# SCH_UD-05-PCB-design-David-Sanchez_2025-.net
KiCad netlist of a schematic drawn in EasyEDA
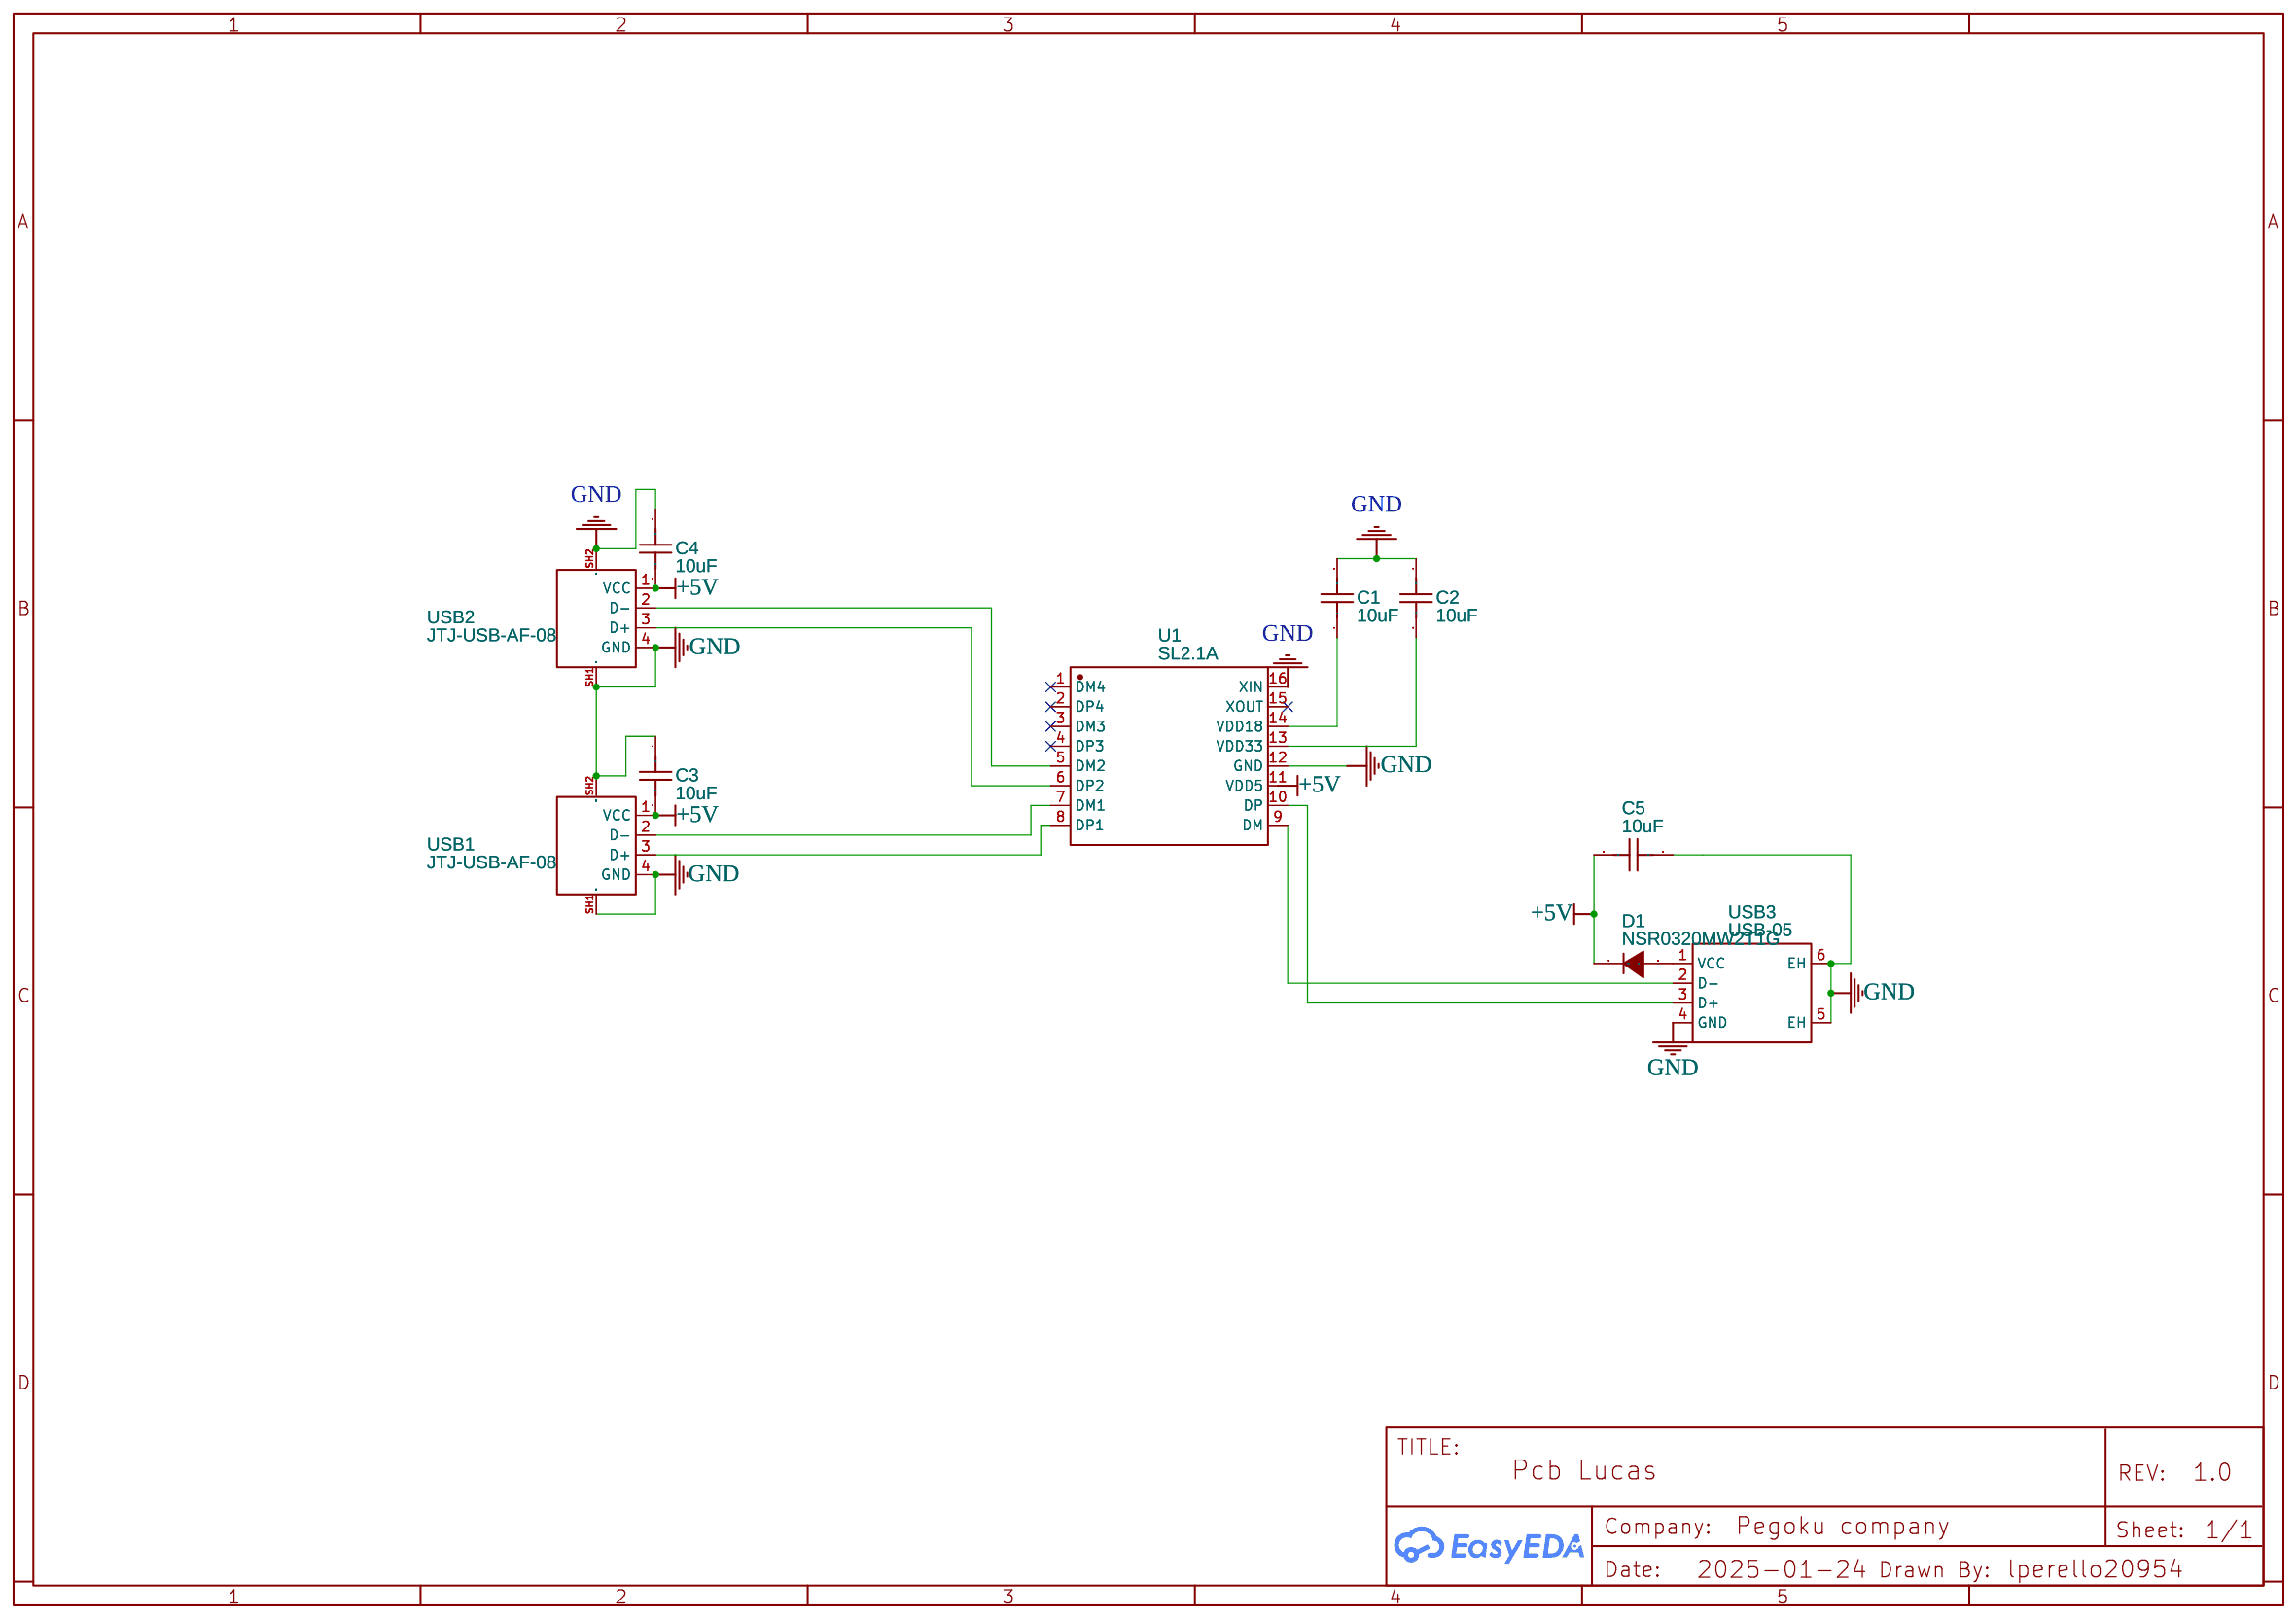
[diagram p0: schematic sheet]

(export (version "E")
  (design (tool "Eeschema 10.0.6"))
  (components
    (comp (ref "C1")
      (value "10uF")
      (fields
        (field (name "Manufacturer Part") "CL10A106KP8NNNC")
        (field (name "Manufacturer") "SAMSUNG(三星)")
      )
      (libsource (lib "") (part "CL10A106KP8NNNC_1"))
    )
    (comp (ref "C2")
      (value "10uF")
      (fields
        (field (name "Manufacturer Part") "CL10A106KP8NNNC")
        (field (name "Manufacturer") "SAMSUNG(三星)")
      )
      (libsource (lib "") (part "CL10A106KP8NNNC"))
    )
    (comp (ref "C3")
      (value "10uF")
      (fields
        (field (name "Manufacturer Part") "CL10A106KP8NNNC")
        (field (name "Manufacturer") "SAMSUNG(三星)")
      )
      (libsource (lib "") (part "CL10A106KP8NNNC"))
    )
    (comp (ref "C4")
      (value "10uF")
      (fields
        (field (name "Manufacturer Part") "CL10A106KP8NNNC")
        (field (name "Manufacturer") "SAMSUNG(三星)")
      )
      (libsource (lib "") (part "CL10A106KP8NNNC"))
    )
    (comp (ref "C5")
      (value "10uF")
      (fields
        (field (name "Manufacturer Part") "CL10A106KP8NNNC")
        (field (name "Manufacturer") "SAMSUNG(三星)")
      )
      (libsource (lib "") (part "CL10A106KP8NNNC_2"))
    )
    (comp (ref "D1")
      (value "NSR0320MW2T1G")
      (fields (field (name "Manufacturer") "onsemi(安森美)"))
      (libsource (lib "") (part "NSR0320MW2T1G"))
    )
    (comp (ref "U1")
      (value "SL2.1A")
      (fields (field (name "Manufacturer") "CoreChips(和芯润德)"))
      (libsource (lib "") (part "SL2.1A"))
    )
    (comp (ref "USB1")
      (value "JTJ-USB-AF-08")
      (fields (field (name "Manufacturer Part") "902-131A1011D10100") (field (name "Manufacturer") "精拓金"))
      (libsource (lib "") (part "JTJ-USB-AF-08"))
    )
    (comp (ref "USB2")
      (value "JTJ-USB-AF-08")
      (fields (field (name "Manufacturer Part") "902-131A1011D10100") (field (name "Manufacturer") "精拓金"))
      (libsource (lib "") (part "JTJ-USB-AF-08"))
    )
    (comp (ref "USB3")
      (value "USB-05")
      (fields (field (name "Manufacturer") "SOFNG(硕方)"))
      (libsource (lib "") (part "USB-05"))
    )
  )
  (nets
    (net (code "1") (name "+5V") (class "Default")
      (node (ref "C3") (pin "2") (pinfunction "2_2") (pintype "unspecified"))
      (node (ref "C4") (pin "2") (pinfunction "2_2") (pintype "unspecified"))
      (node (ref "C5") (pin "2") (pinfunction "2_2") (pintype "unspecified"))
      (node (ref "D1") (pin "1") (pinfunction "C_1") (pintype "unspecified"))
      (node (ref "U1") (pin "11") (pinfunction "VDD5_11") (pintype "unspecified"))
      (node (ref "USB1") (pin "1") (pinfunction "VCC_1") (pintype "input"))
      (node (ref "USB2") (pin "1") (pinfunction "VCC_1") (pintype "input"))
    )
    (net (code "2") (name "GND") (class "Default")
      (node (ref "C1") (pin "2") (pinfunction "2_2") (pintype "unspecified"))
      (node (ref "C2") (pin "1") (pinfunction "1_1") (pintype "unspecified"))
      (node (ref "C3") (pin "1") (pinfunction "1_1") (pintype "unspecified"))
      (node (ref "C4") (pin "1") (pinfunction "1_1") (pintype "unspecified"))
      (node (ref "C5") (pin "1") (pinfunction "1_1") (pintype "unspecified"))
      (node (ref "U1") (pin "12") (pinfunction "GND_12") (pintype "unspecified"))
      (node (ref "U1") (pin "16") (pinfunction "XIN_16") (pintype "unspecified"))
      (node (ref "USB1") (pin "4") (pinfunction "GND_4") (pintype "input"))
      (node (ref "USB1") (pin "SH1") (pinfunction "SH1_SH1") (pintype "unspecified"))
      (node (ref "USB1") (pin "SH2") (pinfunction "SH2_SH2") (pintype "unspecified"))
      (node (ref "USB2") (pin "4") (pinfunction "GND_4") (pintype "input"))
      (node (ref "USB2") (pin "SH1") (pinfunction "SH1_SH1") (pintype "unspecified"))
      (node (ref "USB2") (pin "SH2") (pinfunction "SH2_SH2") (pintype "unspecified"))
      (node (ref "USB3") (pin "4") (pinfunction "GND_4") (pintype "input"))
      (node (ref "USB3") (pin "5") (pinfunction "EH_5") (pintype "unspecified"))
      (node (ref "USB3") (pin "6") (pinfunction "EH_6") (pintype "unspecified"))
    )
    (net (code "3") (name "Net-(D1-A)") (class "Default")
      (node (ref "D1") (pin "2") (pinfunction "A_2") (pintype "unspecified"))
      (node (ref "USB3") (pin "1") (pinfunction "VCC_1") (pintype "input"))
    )
    (net (code "4") (name "Net-(U1-DM)") (class "Default")
      (node (ref "U1") (pin "9") (pinfunction "DM_9") (pintype "unspecified"))
      (node (ref "USB3") (pin "2") (pinfunction "D-_2") (pintype "input"))
    )
    (net (code "5") (name "Net-(U1-DM1)") (class "Default")
      (node (ref "U1") (pin "7") (pinfunction "DM1_7") (pintype "unspecified"))
      (node (ref "USB1") (pin "2") (pinfunction "D-_2") (pintype "input"))
    )
    (net (code "6") (name "Net-(U1-DM2)") (class "Default")
      (node (ref "U1") (pin "5") (pinfunction "DM2_5") (pintype "unspecified"))
      (node (ref "USB2") (pin "2") (pinfunction "D-_2") (pintype "input"))
    )
    (net (code "7") (name "Net-(U1-DP)") (class "Default")
      (node (ref "U1") (pin "10") (pinfunction "DP_10") (pintype "unspecified"))
      (node (ref "USB3") (pin "3") (pinfunction "D+_3") (pintype "input"))
    )
    (net (code "8") (name "Net-(U1-DP1)") (class "Default")
      (node (ref "U1") (pin "8") (pinfunction "DP1_8") (pintype "unspecified"))
      (node (ref "USB1") (pin "3") (pinfunction "D+_3") (pintype "input"))
    )
    (net (code "9") (name "Net-(U1-DP2)") (class "Default")
      (node (ref "U1") (pin "6") (pinfunction "DP2_6") (pintype "unspecified"))
      (node (ref "USB2") (pin "3") (pinfunction "D+_3") (pintype "input"))
    )
    (net (code "10") (name "Net-(U1-VDD18)") (class "Default")
      (node (ref "C1") (pin "1") (pinfunction "1_1") (pintype "unspecified"))
      (node (ref "U1") (pin "14") (pinfunction "VDD18_14") (pintype "unspecified"))
    )
    (net (code "11") (name "Net-(U1-VDD33)") (class "Default")
      (node (ref "C2") (pin "2") (pinfunction "2_2") (pintype "unspecified"))
      (node (ref "U1") (pin "13") (pinfunction "VDD33_13") (pintype "unspecified"))
    )
    (net (code "12") (name "unconnected-(U1-DM3-Pad3)") (class "Default")
      (node (ref "U1") (pin "3") (pinfunction "DM3_3") (pintype "unspecified+no_connect"))
    )
    (net (code "13") (name "unconnected-(U1-DM4-Pad1)") (class "Default")
      (node (ref "U1") (pin "1") (pinfunction "DM4_1") (pintype "unspecified+no_connect"))
    )
    (net (code "14") (name "unconnected-(U1-DP3-Pad4)") (class "Default")
      (node (ref "U1") (pin "4") (pinfunction "DP3_4") (pintype "unspecified+no_connect"))
    )
    (net (code "15") (name "unconnected-(U1-DP4-Pad2)") (class "Default")
      (node (ref "U1") (pin "2") (pinfunction "DP4_2") (pintype "unspecified+no_connect"))
    )
    (net (code "16") (name "unconnected-(U1-XOUT-Pad15)") (class "Default")
      (node (ref "U1") (pin "15") (pinfunction "XOUT_15") (pintype "unspecified+no_connect"))
    )
  )
)
